# Analog_Inputs_10V.net
KiCad netlist of a schematic drawn in Altium Designer
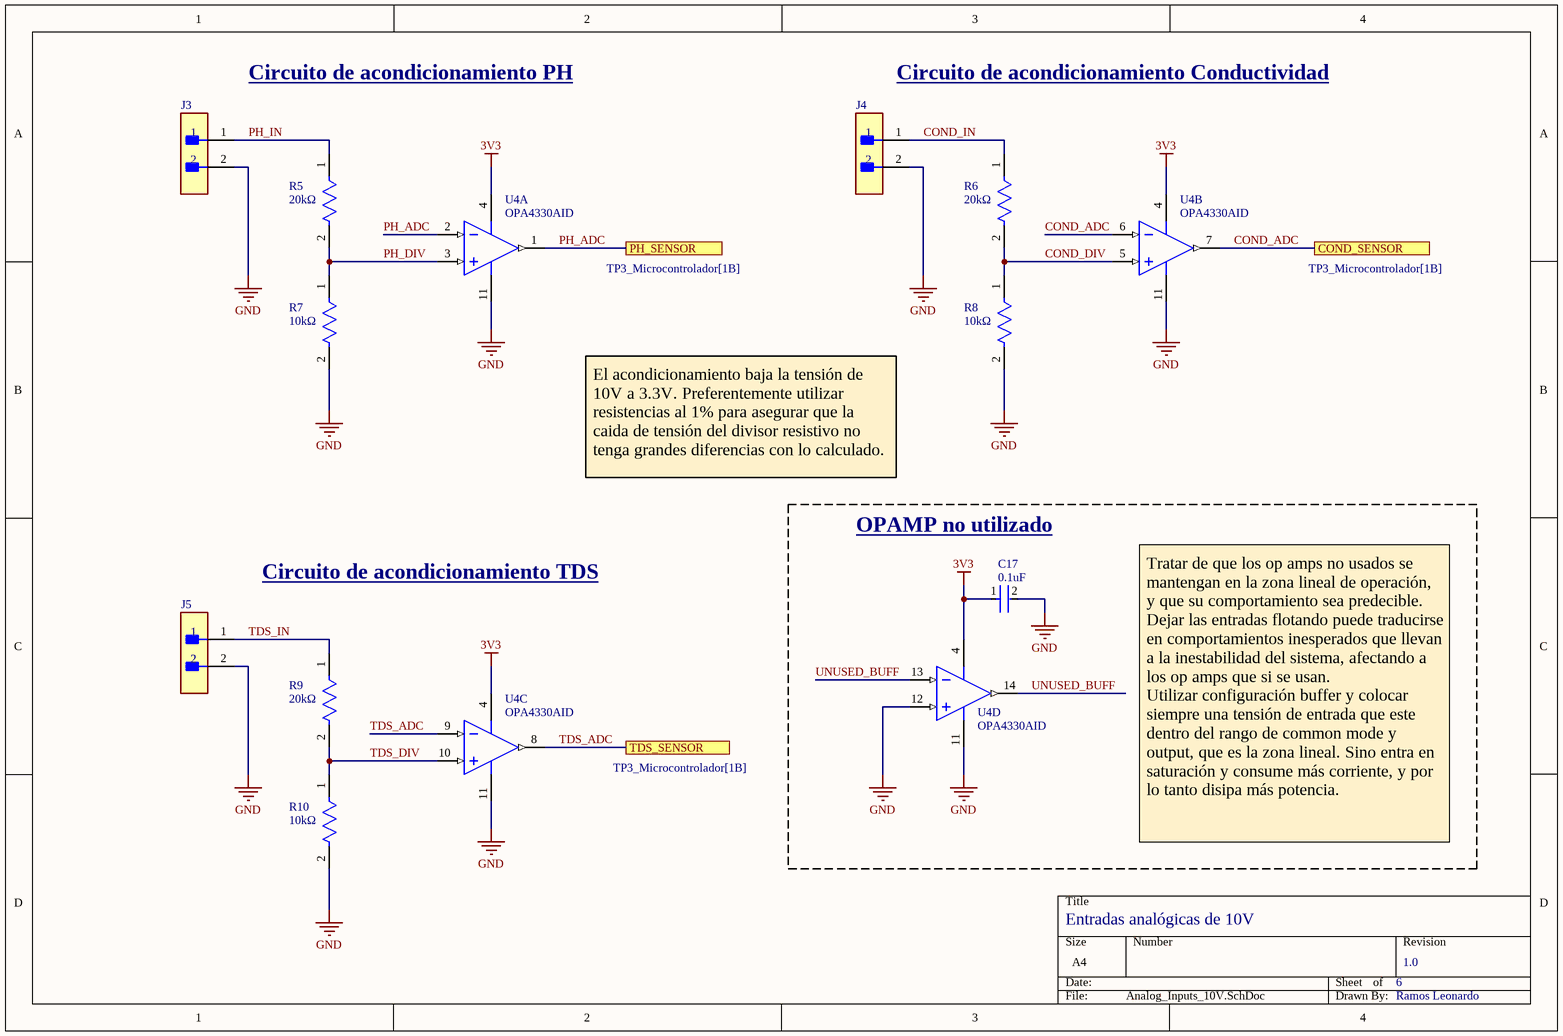
[diagram p0: Analog_Inputs_10V.SchDoc]

(export (version "E")
  (design (tool "Eeschema 10.0.6"))
  (components
    (comp (ref "C17")
      (value "0.1uF")
      (footprint "FP-CC0805-0_85-MFG")
      (description "CAP CER 0.1UF 25V X7R 0805")
      (fields (field (name "MANUFACTURER PART NUMBER") "CC0805KRX7R8BB104") (field (name "TOLERANCE") "0.1"))
      (libsource (lib "Altium Content Vault") (part "11868f565c42a9108669ba33697ecf6"))
    )
    (comp (ref "J3")
      (value "26-60-4020")
      (footprint "FP-26-60-4020-MFG")
      (description "CONN HEADER VERT 2POS 3.96MM")
      (libsource (lib "Altium Content Vault") (part "3bc925449376181038e59eaffc5286c"))
    )
    (comp (ref "J4")
      (value "26-60-4020")
      (footprint "FP-26-60-4020-MFG")
      (description "CONN HEADER VERT 2POS 3.96MM")
      (libsource (lib "Altium Content Vault") (part "3bc925449376181038e59eaffc5286c"))
    )
    (comp (ref "J5")
      (value "26-60-4020")
      (footprint "FP-26-60-4020-MFG")
      (description "CONN HEADER VERT 2POS 3.96MM")
      (libsource (lib "Altium Content Vault") (part "3bc925449376181038e59eaffc5286c"))
    )
    (comp (ref "R5")
      (value "CRCW08054K70JNEA")
      (footprint "FP-CRCW0805-e3-IPC_B")
      (description "RES Thick Film, 10kΩ, 5%, 0.125W, 200ppm/°C, 0805")
      (fields (field (name "TOLERANCE") "5%") (field (name "RESISTANCE") "20kΩ"))
      (libsource (lib "Altium Content Vault") (part "1029c3af85768c4190bb7ad29bc67b5"))
    )
    (comp (ref "R6")
      (value "CRCW08054K70JNEA")
      (footprint "FP-CRCW0805-e3-IPC_B")
      (description "RES Thick Film, 10kΩ, 5%, 0.125W, 200ppm/°C, 0805")
      (fields (field (name "TOLERANCE") "5%") (field (name "RESISTANCE") "20kΩ"))
      (libsource (lib "Altium Content Vault") (part "1029c3af85768c4190bb7ad29bc67b5"))
    )
    (comp (ref "R7")
      (value "CRCW08054K70JNEA")
      (footprint "FP-CRCW0805-e3-IPC_B")
      (description "RES Thick Film, 10kΩ, 5%, 0.125W, 200ppm/°C, 0805")
      (fields (field (name "TOLERANCE") "5%") (field (name "RESISTANCE") "10kΩ"))
      (libsource (lib "Altium Content Vault") (part "1029c3af85768c4190bb7ad29bc67b5"))
    )
    (comp (ref "R8")
      (value "CRCW08054K70JNEA")
      (footprint "FP-CRCW0805-e3-IPC_B")
      (description "RES Thick Film, 10kΩ, 5%, 0.125W, 200ppm/°C, 0805")
      (fields (field (name "TOLERANCE") "5%") (field (name "RESISTANCE") "10kΩ"))
      (libsource (lib "Altium Content Vault") (part "1029c3af85768c4190bb7ad29bc67b5"))
    )
    (comp (ref "R9")
      (value "CRCW08054K70JNEA")
      (footprint "FP-CRCW0805-e3-IPC_B")
      (description "RES Thick Film, 10kΩ, 5%, 0.125W, 200ppm/°C, 0805")
      (fields (field (name "TOLERANCE") "5%") (field (name "RESISTANCE") "20kΩ"))
      (libsource (lib "Altium Content Vault") (part "1029c3af85768c4190bb7ad29bc67b5"))
    )
    (comp (ref "R10")
      (value "CRCW08054K70JNEA")
      (footprint "FP-CRCW0805-e3-IPC_B")
      (description "RES Thick Film, 10kΩ, 5%, 0.125W, 200ppm/°C, 0805")
      (fields (field (name "TOLERANCE") "5%") (field (name "RESISTANCE") "10kΩ"))
      (libsource (lib "Altium Content Vault") (part "1029c3af85768c4190bb7ad29bc67b5"))
    )
    (comp (ref "U4")
      (value "OPA4330AID")
      (footprint "D0014A_N")
      (fields (field (name "MANUFACTURER") "Texas Instruments"))
      (libsource (lib "Altium Content Vault") (part "TI-OPA16X4_4XXX-14"))
    )
  )
  (nets
    (net (code "1") (name "/COND_ADC") (class "Default")
      (node (ref "U4") (pin "6") (pinfunction "IN_B-_6") (pintype "input"))
      (node (ref "U4") (pin "7") (pinfunction "OUT_B_7") (pintype "output"))
    )
    (net (code "2") (name "/COND_DIV") (class "Default")
      (node (ref "R6") (pin "2") (pinfunction "2_2") (pintype "passive"))
      (node (ref "R8") (pin "1") (pinfunction "1_1") (pintype "passive"))
      (node (ref "U4") (pin "5") (pinfunction "IN_B+_5") (pintype "input"))
    )
    (net (code "3") (name "/COND_IN") (class "Default")
      (node (ref "J4") (pin "1") (pinfunction "1_1") (pintype "passive"))
      (node (ref "R6") (pin "1") (pinfunction "1_1") (pintype "passive"))
    )
    (net (code "4") (name "/PH_ADC") (class "Default")
      (node (ref "U4") (pin "1") (pinfunction "OUT_A_1") (pintype "output"))
      (node (ref "U4") (pin "2") (pinfunction "IN_A-_2") (pintype "input"))
    )
    (net (code "5") (name "/PH_DIV") (class "Default")
      (node (ref "R5") (pin "2") (pinfunction "2_2") (pintype "passive"))
      (node (ref "R7") (pin "1") (pinfunction "1_1") (pintype "passive"))
      (node (ref "U4") (pin "3") (pinfunction "IN_A+_3") (pintype "input"))
    )
    (net (code "6") (name "/PH_IN") (class "Default")
      (node (ref "J3") (pin "1") (pinfunction "1_1") (pintype "passive"))
      (node (ref "R5") (pin "1") (pinfunction "1_1") (pintype "passive"))
    )
    (net (code "7") (name "/TDS_ADC") (class "Default")
      (node (ref "U4") (pin "8") (pinfunction "OUT_C_8") (pintype "output"))
      (node (ref "U4") (pin "9") (pinfunction "IN_C-_9") (pintype "input"))
    )
    (net (code "8") (name "/TDS_DIV") (class "Default")
      (node (ref "R10") (pin "1") (pinfunction "1_1") (pintype "passive"))
      (node (ref "R9") (pin "2") (pinfunction "2_2") (pintype "passive"))
      (node (ref "U4") (pin "10") (pinfunction "IN_C+_10") (pintype "input"))
    )
    (net (code "9") (name "/TDS_IN") (class "Default")
      (node (ref "J5") (pin "1") (pinfunction "1_1") (pintype "passive"))
      (node (ref "R9") (pin "1") (pinfunction "1_1") (pintype "passive"))
    )
    (net (code "10") (name "/UNUSED_BUFF") (class "Default")
      (node (ref "U4") (pin "13") (pinfunction "IN_D-_13") (pintype "input"))
      (node (ref "U4") (pin "14") (pinfunction "OUT_D_14") (pintype "output"))
    )
    (net (code "11") (name "3V3") (class "Default")
      (node (ref "C17") (pin "1") (pinfunction "1_1") (pintype "passive"))
      (node (ref "U4") (pin "4") (pinfunction "V+_4") (pintype "power_in"))
    )
    (net (code "12") (name "GND") (class "Default")
      (node (ref "C17") (pin "2") (pinfunction "2_2") (pintype "passive"))
      (node (ref "J3") (pin "2") (pinfunction "2_2") (pintype "passive"))
      (node (ref "J4") (pin "2") (pinfunction "2_2") (pintype "passive"))
      (node (ref "J5") (pin "2") (pinfunction "2_2") (pintype "passive"))
      (node (ref "R10") (pin "2") (pinfunction "2_2") (pintype "passive"))
      (node (ref "R7") (pin "2") (pinfunction "2_2") (pintype "passive"))
      (node (ref "R8") (pin "2") (pinfunction "2_2") (pintype "passive"))
      (node (ref "U4") (pin "11") (pinfunction "V-_11") (pintype "power_in"))
      (node (ref "U4") (pin "12") (pinfunction "IN_D+_12") (pintype "input"))
    )
  )
)
